# MCU.net
KiCad netlist of a schematic drawn in Altium Designer
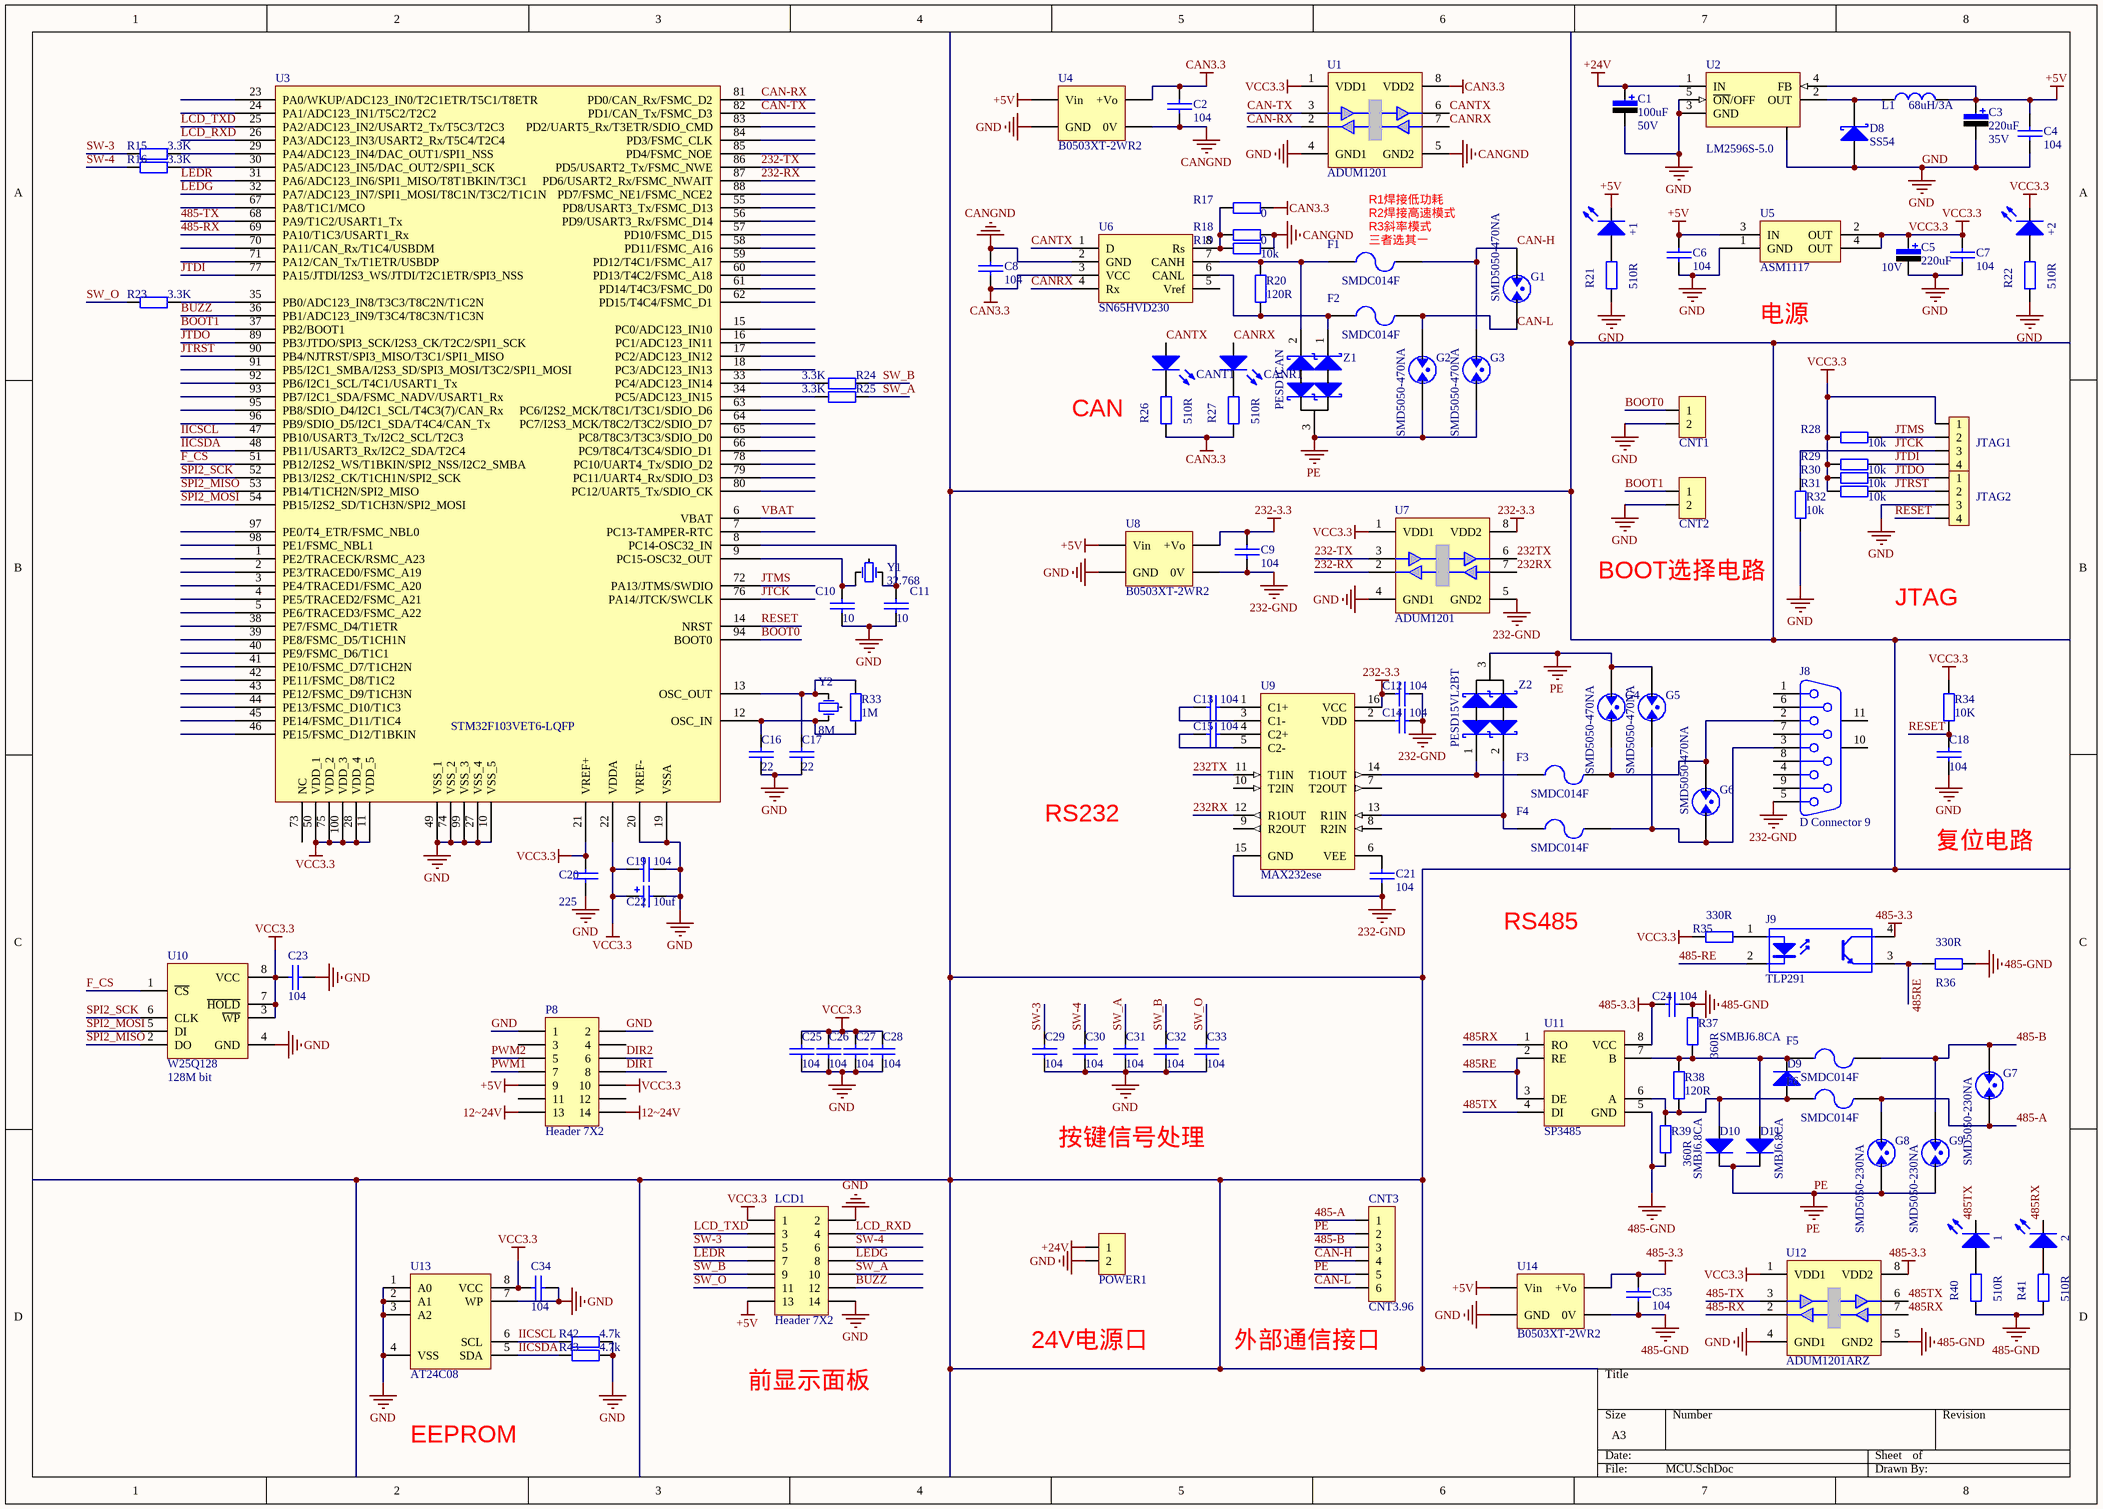
[diagram p0: MCU.SchDoc]

(export (version "E")
  (design (tool "Eeschema 10.0.6"))
  (components
    (comp (ref "+1") (value "COLOUR") (footprint "0603LED") (libsource (lib "MY_Library") (part "ledφ6")))
    (comp (ref "+2") (value "COLOUR") (footprint "0603LED") (libsource (lib "MY_Library") (part "ledφ6")))
    (comp (ref "1") (value "COLOUR") (footprint "0603LED") (libsource (lib "MY_Library") (part "ledφ6")))
    (comp (ref "2") (value "COLOUR") (footprint "0603LED") (libsource (lib "MY_Library") (part "ledφ6")))
    (comp (ref "C1")
      (value "100uF")
      (footprint "C-RB-S10")
      (description "极性电解电容")
      (fields
        (field (name "VOL") "50V")
        (field (name "Comment") "Cap Pol")
        (field (name "PUBLISHER") "Altium Limited")
      )
      (libsource (lib "Fszhang") (part "Cap Pol"))
    )
    (comp (ref "C2")
      (value "104")
      (footprint "0603C")
      (description "安规电容")
      (libsource (lib "MY_Library") (part "CAP X"))
    )
    (comp (ref "C3")
      (value "220uF")
      (footprint "C-RB-S10")
      (description "极性电解电容")
      (fields
        (field (name "VOL") "35V")
        (field (name "Comment") "Cap Pol")
        (field (name "PUBLISHER") "Altium Limited")
      )
      (libsource (lib "Fszhang") (part "Cap Pol"))
    )
    (comp (ref "C4")
      (value "104")
      (footprint "0603C")
      (description "安规电容")
      (libsource (lib "MY_Library") (part "CAP X"))
    )
    (comp (ref "C5")
      (value "220uF")
      (footprint "CAP-7343")
      (description "极性电解电容")
      (fields
        (field (name "VOL") "10V")
        (field (name "Comment") "Cap Pol")
        (field (name "PUBLISHER") "Altium Limited")
      )
      (libsource (lib "Fszhang") (part "Cap Pol"))
    )
    (comp (ref "C6")
      (value "104")
      (footprint "0603C")
      (description "安规电容")
      (libsource (lib "MY_Library") (part "CAP X"))
    )
    (comp (ref "C7")
      (value "104")
      (footprint "0603C")
      (description "安规电容")
      (libsource (lib "MY_Library") (part "CAP X"))
    )
    (comp (ref "C8")
      (value "104")
      (footprint "0603C")
      (description "安规电容")
      (libsource (lib "MY_Library") (part "CAP X"))
    )
    (comp (ref "C9")
      (value "104")
      (footprint "0603C")
      (description "安规电容")
      (libsource (lib "MY_Library") (part "CAP X"))
    )
    (comp (ref "C10")
      (value "10")
      (footprint "0603C")
      (description "安规电容")
      (libsource (lib "MY_Library") (part "CAP X"))
    )
    (comp (ref "C11")
      (value "10")
      (footprint "0603C")
      (description "安规电容")
      (libsource (lib "MY_Library") (part "CAP X"))
    )
    (comp (ref "C12")
      (value "104")
      (footprint "0603C")
      (description "安规电容")
      (libsource (lib "MY_Library") (part "CAP X"))
    )
    (comp (ref "C13")
      (value "104")
      (footprint "0603C")
      (description "安规电容")
      (libsource (lib "MY_Library") (part "CAP X"))
    )
    (comp (ref "C14")
      (value "104")
      (footprint "0603C")
      (description "安规电容")
      (libsource (lib "MY_Library") (part "CAP X"))
    )
    (comp (ref "C15")
      (value "104")
      (footprint "0603C")
      (description "安规电容")
      (libsource (lib "MY_Library") (part "CAP X"))
    )
    (comp (ref "C16")
      (value "22")
      (footprint "0603C")
      (description "安规电容")
      (libsource (lib "MY_Library") (part "CAP X"))
    )
    (comp (ref "C17")
      (value "22")
      (footprint "0603C")
      (description "安规电容")
      (libsource (lib "MY_Library") (part "CAP X"))
    )
    (comp (ref "C18")
      (value "104")
      (footprint "0603C")
      (description "安规电容")
      (libsource (lib "MY_Library") (part "CAP X"))
    )
    (comp (ref "C19")
      (value "104")
      (footprint "0603C")
      (description "安规电容")
      (libsource (lib "MY_Library") (part "CAP X"))
    )
    (comp (ref "C20")
      (value "225")
      (footprint "0603C")
      (description "安规电容")
      (libsource (lib "MY_Library") (part "CAP X"))
    )
    (comp (ref "C21")
      (value "104")
      (footprint "0603C")
      (description "安规电容")
      (libsource (lib "MY_Library") (part "CAP X"))
    )
    (comp (ref "C22")
      (value "10uf")
      (footprint "ct3216-18")
      (description "电解电容")
      (libsource (lib "MY_Library") (part "CAP"))
    )
    (comp (ref "C23")
      (value "104")
      (footprint "0603C")
      (description "安规电容")
      (libsource (lib "MY_Library") (part "CAP X"))
    )
    (comp (ref "C24")
      (value "104")
      (footprint "0603C")
      (description "安规电容")
      (libsource (lib "MY_Library") (part "CAP X"))
    )
    (comp (ref "C25")
      (value "104")
      (footprint "0603C")
      (description "安规电容")
      (libsource (lib "MY_Library") (part "CAP X"))
    )
    (comp (ref "C26")
      (value "104")
      (footprint "0603C")
      (description "安规电容")
      (libsource (lib "MY_Library") (part "CAP X"))
    )
    (comp (ref "C27")
      (value "104")
      (footprint "0603C")
      (description "安规电容")
      (libsource (lib "MY_Library") (part "CAP X"))
    )
    (comp (ref "C28")
      (value "104")
      (footprint "0603C")
      (description "安规电容")
      (libsource (lib "MY_Library") (part "CAP X"))
    )
    (comp (ref "C29")
      (value "104")
      (footprint "0603C")
      (description "安规电容")
      (libsource (lib "MY_Library") (part "CAP X"))
    )
    (comp (ref "C30")
      (value "104")
      (footprint "0603C")
      (description "安规电容")
      (libsource (lib "MY_Library") (part "CAP X"))
    )
    (comp (ref "C31")
      (value "104")
      (footprint "0603C")
      (description "安规电容")
      (libsource (lib "MY_Library") (part "CAP X"))
    )
    (comp (ref "C32")
      (value "104")
      (footprint "0603C")
      (description "安规电容")
      (libsource (lib "MY_Library") (part "CAP X"))
    )
    (comp (ref "C33")
      (value "104")
      (footprint "0603C")
      (description "安规电容")
      (libsource (lib "MY_Library") (part "CAP X"))
    )
    (comp (ref "C34")
      (value "104")
      (footprint "0603C")
      (description "安规电容")
      (libsource (lib "MY_Library") (part "CAP X"))
    )
    (comp (ref "C35")
      (value "104")
      (footprint "0603C")
      (description "安规电容")
      (libsource (lib "MY_Library") (part "CAP X"))
    )
    (comp (ref "CANR1") (value "COLOUR") (footprint "0603LED") (libsource (lib "MY_Library") (part "ledφ6")))
    (comp (ref "CANT1") (value "COLOUR") (footprint "0603LED") (libsource (lib "MY_Library") (part "ledφ6")))
    (comp (ref "CNT1") (value "cnt2p") (footprint "cont-1") (libsource (lib "MY_Library") (part "cnt2p")))
    (comp (ref "CNT2") (value "cnt2p") (footprint "cont-1") (libsource (lib "MY_Library") (part "cnt2p")))
    (comp (ref "CNT3")
      (value "CNT3.96")
      (footprint "CNT3.96")
      (description "接线端子(3.96MM)")
      (libsource (lib "MY_Library") (part "CNT3.96"))
    )
    (comp (ref "D8")
      (value "D-Schottky")
      (footprint "DIODE-SMA")
      (description "肖特基二极管")
      (fields (field (name "TYPE") "SS54") (field (name "PUBLISHER") "Altium Limited"))
      (libsource (lib "Fszhang") (part "D-Schottky"))
    )
    (comp (ref "D9")
      (value "TVS")
      (footprint "DIODE-SMB")
      (description "TVS保护")
      (fields (field (name "TYPE") "SMBJ6.8CA") (field (name "PUBLISHER") "Altium Limited"))
      (libsource (lib "Fszhang") (part "TVS"))
    )
    (comp (ref "D10")
      (value "TVS")
      (footprint "DIODE-SMB")
      (description "TVS保护")
      (fields (field (name "TYPE") "SMBJ6.8CA") (field (name "PUBLISHER") "Altium Limited"))
      (libsource (lib "Fszhang") (part "TVS"))
    )
    (comp (ref "D11")
      (value "TVS")
      (footprint "DIODE-SMB")
      (description "TVS保护")
      (fields (field (name "TYPE") "SMBJ6.8CA") (field (name "PUBLISHER") "Altium Limited"))
      (libsource (lib "Fszhang") (part "TVS"))
    )
    (comp (ref "F1")
      (value "SMDC014F")
      (footprint "1812")
      (description "保险丝")
      (fields (field (name "PUBLISHER") "Altium Limited"))
      (libsource (lib "Fszhang") (part "Fuse 2"))
    )
    (comp (ref "F2")
      (value "SMDC014F")
      (footprint "1812")
      (description "保险丝")
      (fields (field (name "Comment") "Fuse") (field (name "PUBLISHER") "Altium Limited"))
      (libsource (lib "Fszhang") (part "Fuse 2"))
    )
    (comp (ref "F3")
      (value "SMDC014F")
      (footprint "1812")
      (description "保险丝")
      (fields (field (name "PUBLISHER") "Altium Limited"))
      (libsource (lib "Fszhang") (part "Fuse 2"))
    )
    (comp (ref "F4")
      (value "SMDC014F")
      (footprint "1812")
      (description "保险丝")
      (fields (field (name "Comment") "Fuse") (field (name "PUBLISHER") "Altium Limited"))
      (libsource (lib "Fszhang") (part "Fuse 2"))
    )
    (comp (ref "F5")
      (value "SMDC014F")
      (footprint "1812")
      (description "保险丝")
      (fields (field (name "PUBLISHER") "Altium Limited"))
      (libsource (lib "Fszhang") (part "Fuse 2"))
    )
    (comp (ref "F6")
      (value "SMDC014F")
      (footprint "1812")
      (description "保险丝")
      (fields (field (name "Comment") "Fuse") (field (name "PUBLISHER") "Altium Limited"))
      (libsource (lib "Fszhang") (part "Fuse 2"))
    )
    (comp (ref "G1")
      (value "SMD5050-470NA")
      (footprint "SMD5050")
      (description "230V 气体放电管")
      (libsource (lib "Fszhang") (part "SMD5050-230NA"))
    )
    (comp (ref "G2")
      (value "SMD5050-470NA")
      (footprint "SMD5050")
      (description "230V 气体放电管")
      (libsource (lib "Fszhang") (part "SMD5050-230NA"))
    )
    (comp (ref "G3")
      (value "SMD5050-470NA")
      (footprint "SMD5050")
      (description "230V 气体放电管")
      (libsource (lib "Fszhang") (part "SMD5050-230NA"))
    )
    (comp (ref "G4")
      (value "SMD5050-470NA")
      (footprint "SMD5050")
      (description "230V 气体放电管")
      (libsource (lib "Fszhang") (part "SMD5050-230NA"))
    )
    (comp (ref "G5")
      (value "SMD5050-470NA")
      (footprint "SMD5050")
      (description "230V 气体放电管")
      (libsource (lib "Fszhang") (part "SMD5050-230NA"))
    )
    (comp (ref "G6")
      (value "SMD5050-470NA")
      (footprint "SMD5050")
      (description "230V 气体放电管")
      (libsource (lib "Fszhang") (part "SMD5050-230NA"))
    )
    (comp (ref "G7")
      (value "SMD5050-230NA")
      (footprint "SMD5050")
      (description "230V 气体放电管")
      (libsource (lib "Fszhang") (part "SMD5050-230NA"))
    )
    (comp (ref "G8")
      (value "SMD5050-230NA")
      (footprint "SMD5050")
      (description "230V 气体放电管")
      (libsource (lib "Fszhang") (part "SMD5050-230NA"))
    )
    (comp (ref "G9")
      (value "SMD5050-230NA")
      (footprint "SMD5050")
      (description "230V 气体放电管")
      (libsource (lib "Fszhang") (part "SMD5050-230NA"))
    )
    (comp (ref "J8")
      (value "D Connector 9")
      (footprint "DB9-M")
      (description "串口")
      (fields (field (name "PUBLISHER") "Altium Limited"))
      (libsource (lib "Fszhang") (part "D Connector 9"))
    )
    (comp (ref "J9")
      (value "TLP291")
      (footprint "SOP127P710X350-4N")
      (description "光耦")
      (fields (field (name "PUBLISHER") "Altium Limited"))
      (libsource (lib "Fszhang") (part "TLP281"))
    )
    (comp (ref "JTAG1")
      (value "单排插针11mm4p")
      (footprint "单排插针2.54")
      (libsource (lib "MY_Library") (part "单排插针11mm4p"))
    )
    (comp (ref "JTAG2")
      (value "单排插针11mm4p")
      (footprint "单排插针2.54")
      (libsource (lib "MY_Library") (part "单排插针11mm4p"))
    )
    (comp (ref "L1")
      (value "68uH/3A")
      (footprint "L-SMD-12")
      (description "电感")
      (fields (field (name "Comment") "Inductor") (field (name "PUBLISHER") "Altium Limited"))
      (libsource (lib "Fszhang") (part "Inductor"))
    )
    (comp (ref "LCD1")
      (value "Header 7X2")
      (footprint "HDR7X2_A1")
      (description "Header, 7-Pin")
      (fields (field (name "PUBLISHER") "Altium Limited"))
      (libsource (lib "Fszhang") (part "Header 7X2"))
    )
    (comp (ref "P8")
      (value "Header 7X2")
      (footprint "HDR7X2_A1")
      (description "Header, 7-Pin")
      (fields (field (name "PUBLISHER") "Altium Limited"))
      (libsource (lib "Fszhang") (part "Header 7X2"))
    )
    (comp (ref "POWER1")
      (value "CNT5.08MM*2 WAN")
      (footprint "CNT5.08*2WAN")
      (libsource (lib "MY_Library") (part "CNT5.08MM*2 WAN"))
    )
    (comp (ref "R15")
      (value "3.3K")
      (footprint "0603-1")
      (description "贴片电阻")
      (fields (field (name "Comment") "Res1") (field (name "PUBLISHER") "Altium Limited"))
      (libsource (lib "") (part "Res1_1"))
    )
    (comp (ref "R16")
      (value "3.3K")
      (footprint "0603-1")
      (description "贴片电阻")
      (fields (field (name "Comment") "Res1") (field (name "PUBLISHER") "Altium Limited"))
      (libsource (lib "") (part "Res1_1"))
    )
    (comp (ref "R17")
      (value "0")
      (footprint "0603-1")
      (description "贴片电阻")
      (fields (field (name "Comment") "Res1") (field (name "PUBLISHER") "Altium Limited"))
      (libsource (lib "") (part "Res1_1"))
    )
    (comp (ref "R18")
      (value "0")
      (footprint "0603-1")
      (description "贴片电阻")
      (fields (field (name "Comment") "Res1") (field (name "PUBLISHER") "Altium Limited"))
      (libsource (lib "") (part "Res1_1"))
    )
    (comp (ref "R19")
      (value "10k")
      (footprint "0603-1")
      (description "贴片电阻")
      (fields (field (name "Comment") "Res1") (field (name "PUBLISHER") "Altium Limited"))
      (libsource (lib "") (part "Res1_1"))
    )
    (comp (ref "R20")
      (value "120R")
      (footprint "0603-1")
      (description "贴片电阻")
      (fields (field (name "Comment") "Res1") (field (name "PUBLISHER") "Altium Limited"))
      (libsource (lib "Fszhang") (part "Res1"))
    )
    (comp (ref "R21")
      (value "510R")
      (footprint "0603-1")
      (description "贴片电阻")
      (fields (field (name "Comment") "Res1") (field (name "PUBLISHER") "Altium Limited"))
      (libsource (lib "Fszhang") (part "Res1"))
    )
    (comp (ref "R22")
      (value "510R")
      (footprint "0603-1")
      (description "贴片电阻")
      (fields (field (name "Comment") "Res1") (field (name "PUBLISHER") "Altium Limited"))
      (libsource (lib "Fszhang") (part "Res1"))
    )
    (comp (ref "R23")
      (value "3.3K")
      (footprint "0603-1")
      (description "贴片电阻")
      (fields (field (name "Comment") "Res1") (field (name "PUBLISHER") "Altium Limited"))
      (libsource (lib "") (part "Res1_1"))
    )
    (comp (ref "R24")
      (value "3.3K")
      (footprint "0603-1")
      (description "贴片电阻")
      (fields (field (name "Comment") "Res1") (field (name "PUBLISHER") "Altium Limited"))
      (libsource (lib "") (part "Res1_2"))
    )
    (comp (ref "R25")
      (value "3.3K")
      (footprint "0603-1")
      (description "贴片电阻")
      (fields (field (name "Comment") "Res1") (field (name "PUBLISHER") "Altium Limited"))
      (libsource (lib "") (part "Res1_2"))
    )
    (comp (ref "R26")
      (value "510R")
      (footprint "0603-1")
      (description "贴片电阻")
      (fields (field (name "Comment") "Res1") (field (name "PUBLISHER") "Altium Limited"))
      (libsource (lib "Fszhang") (part "Res1"))
    )
    (comp (ref "R27")
      (value "510R")
      (footprint "0603-1")
      (description "贴片电阻")
      (fields (field (name "Comment") "Res1") (field (name "PUBLISHER") "Altium Limited"))
      (libsource (lib "Fszhang") (part "Res1"))
    )
    (comp (ref "R28")
      (value "10k")
      (footprint "0603-1")
      (description "贴片电阻")
      (fields (field (name "Comment") "Res1") (field (name "PUBLISHER") "Altium Limited"))
      (libsource (lib "") (part "Res1_1"))
    )
    (comp (ref "R29")
      (value "10k")
      (footprint "0603-1")
      (description "贴片电阻")
      (fields (field (name "Comment") "Res1") (field (name "PUBLISHER") "Altium Limited"))
      (libsource (lib "") (part "Res1_1"))
    )
    (comp (ref "R30")
      (value "10k")
      (footprint "0603-1")
      (description "贴片电阻")
      (fields (field (name "Comment") "Res1") (field (name "PUBLISHER") "Altium Limited"))
      (libsource (lib "") (part "Res1_1"))
    )
    (comp (ref "R31")
      (value "10k")
      (footprint "0603-1")
      (description "贴片电阻")
      (fields (field (name "Comment") "Res1") (field (name "PUBLISHER") "Altium Limited"))
      (libsource (lib "") (part "Res1_1"))
    )
    (comp (ref "R32")
      (value "10k")
      (footprint "0603-1")
      (description "贴片电阻")
      (fields (field (name "Comment") "Res1") (field (name "PUBLISHER") "Altium Limited"))
      (libsource (lib "") (part "Res1_3"))
    )
    (comp (ref "R33")
      (value "1M")
      (footprint "0603-1")
      (description "贴片电阻")
      (fields (field (name "Comment") "Res1") (field (name "PUBLISHER") "Altium Limited"))
      (libsource (lib "Fszhang") (part "Res1"))
    )
    (comp (ref "R34")
      (value "10K")
      (footprint "0603-1")
      (description "贴片电阻")
      (fields (field (name "Comment") "Res1") (field (name "PUBLISHER") "Altium Limited"))
      (libsource (lib "Fszhang") (part "Res1"))
    )
    (comp (ref "R35")
      (value "330R")
      (footprint "0603-1")
      (description "贴片电阻")
      (fields (field (name "Comment") "Res1") (field (name "PUBLISHER") "Altium Limited"))
      (libsource (lib "") (part "Res1_1"))
    )
    (comp (ref "R36")
      (value "330R")
      (footprint "0603-1")
      (description "贴片电阻")
      (fields (field (name "Comment") "Res1") (field (name "PUBLISHER") "Altium Limited"))
      (libsource (lib "") (part "Res1_1"))
    )
    (comp (ref "R37")
      (value "360R")
      (footprint "0603-1")
      (description "贴片电阻")
      (fields (field (name "Comment") "Res1") (field (name "PUBLISHER") "Altium Limited"))
      (libsource (lib "Fszhang") (part "Res1"))
    )
    (comp (ref "R38")
      (value "120R")
      (footprint "0603-1")
      (description "贴片电阻")
      (fields (field (name "Comment") "Res1") (field (name "PUBLISHER") "Altium Limited"))
      (libsource (lib "Fszhang") (part "Res1"))
    )
    (comp (ref "R39")
      (value "360R")
      (footprint "0603-1")
      (description "贴片电阻")
      (fields (field (name "Comment") "Res1") (field (name "PUBLISHER") "Altium Limited"))
      (libsource (lib "Fszhang") (part "Res1"))
    )
    (comp (ref "R40")
      (value "510R")
      (footprint "0603-1")
      (description "贴片电阻")
      (fields (field (name "Comment") "Res1") (field (name "PUBLISHER") "Altium Limited"))
      (libsource (lib "Fszhang") (part "Res1"))
    )
    (comp (ref "R41")
      (value "510R")
      (footprint "0603-1")
      (description "贴片电阻")
      (fields (field (name "Comment") "Res1") (field (name "PUBLISHER") "Altium Limited"))
      (libsource (lib "Fszhang") (part "Res1"))
    )
    (comp (ref "R42")
      (value "4.7k")
      (footprint "0603-1")
      (description "贴片电阻")
      (fields (field (name "Comment") "Res1") (field (name "PUBLISHER") "Altium Limited"))
      (libsource (lib "") (part "Res1_1"))
    )
    (comp (ref "R43")
      (value "4.7k")
      (footprint "0603-1")
      (description "贴片电阻")
      (fields (field (name "Comment") "Res1") (field (name "PUBLISHER") "Altium Limited"))
      (libsource (lib "") (part "Res1_1"))
    )
    (comp (ref "U1")
      (value "ADUM1201")
      (footprint "NSO8_N")
      (description "ADI隔离芯片")
      (libsource (lib "Fszhang") (part "ADUM1201"))
    )
    (comp (ref "U2")
      (value "LM2596S-5.0")
      (footprint "TO-263-5")
      (description "5V稳压芯片")
      (fields (field (name "PUBLISHER") "Altium Limited"))
      (libsource (lib "Fszhang") (part "LM2596S-5.0"))
    )
    (comp (ref "U3")
      (value "STM32F103VET6-LQFP")
      (footprint "LQFP-100_M")
      (description "STM32单片机100引脚")
      (libsource (lib "Fszhang") (part "STM32F103V"))
    )
    (comp (ref "U4")
      (value "B0503XT-2WR2")
      (footprint "B_XT-2WR2")
      (description "5v-3.3v-2w隔离电源")
      (libsource (lib "Fszhang") (part "B0503D-2WR2"))
    )
    (comp (ref "U5")
      (value "ASM1117")
      (footprint "SOT-223")
      (description "3.3V稳压芯片")
      (libsource (lib "Fszhang") (part "ASM1117"))
    )
    (comp (ref "U6")
      (value "SN65HVD230")
      (footprint "NSO8_N")
      (description "CAN芯片")
      (libsource (lib "Fszhang") (part "SN65HVD230"))
    )
    (comp (ref "U7")
      (value "ADUM1201")
      (footprint "NSO8_N")
      (description "ADI隔离芯片")
      (libsource (lib "Fszhang") (part "ADUM1201"))
    )
    (comp (ref "U8")
      (value "B0503XT-2WR2")
      (footprint "B_XT-2WR2")
      (description "5v-3.3v-2w隔离电源")
      (libsource (lib "Fszhang") (part "B0503D-2WR2"))
    )
    (comp (ref "U9")
      (value "MAX232ese")
      (footprint "NSO16_M")
      (description "+5V Powered, Multi-Channel RS-232 Driver/Receiver")
      (fields (field (name "PUBLISHER") "Altium Limited"))
      (libsource (lib "Fszhang") (part "MAX232"))
    )
    (comp (ref "U10")
      (value "W25Q128")
      (footprint "SOIC8_W")
      (description "SPI FLASH")
      (fields (field (name "MEMORY") "128M bit"))
      (libsource (lib "Fszhang") (part "W25QXX"))
    )
    (comp (ref "U11")
      (value "SP3485")
      (footprint "NSO8_N")
      (description "485总线芯片")
      (libsource (lib "Fszhang") (part "SP3485"))
    )
    (comp (ref "U12")
      (value "ADUM1201ARZ")
      (footprint "NSO8_N")
      (description "ADI隔离芯片")
      (libsource (lib "Fszhang") (part "ADUM1201"))
    )
    (comp (ref "U13")
      (value "AT24C08")
      (footprint "SOIC8_N")
      (description "EEROM存储器")
      (libsource (lib "Fszhang") (part "AT24C02"))
    )
    (comp (ref "U14")
      (value "B0503XT-2WR2")
      (footprint "B_XT-2WR2")
      (description "5v-3.3v-2w隔离电源")
      (libsource (lib "Fszhang") (part "B0503D-2WR2"))
    )
    (comp (ref "Y1")
      (value "32.768")
      (footprint "MC-146")
      (description "圆柱晶振")
      (fields (field (name "Comment") "XTAL_SM") (field (name "PUBLISHER") "Altium Limited"))
      (libsource (lib "Fszhang") (part "XTAL_SM"))
    )
    (comp (ref "Y2")
      (value "8M")
      (footprint "xtal3225")
      (description "圆柱晶振")
      (fields (field (name "Comment") "XTAL_SM") (field (name "PUBLISHER") "Altium Limited"))
      (libsource (lib "Fszhang") (part "XTAL_SM"))
    )
    (comp (ref "Z1")
      (value "PESD1CAN")
      (footprint "SOT-23")
      (description "过压保护")
      (libsource (lib "Fszhang") (part "PESD1CAN"))
    )
    (comp (ref "Z2")
      (value "PESD15VL2BT")
      (footprint "SOT-23")
      (description "过压保护")
      (libsource (lib "Fszhang") (part "PESD1CAN"))
    )
  )
  (nets
    (net (code "1") (name "+5V") (class "Default")
      (node (ref "+1") (pin "2") (pinfunction "-_2") (pintype "passive"))
      (node (ref "C3") (pin "1") (pinfunction "1_1") (pintype "passive"))
      (node (ref "C4") (pin "1") (pinfunction "1_1") (pintype "passive"))
      (node (ref "C6") (pin "1") (pinfunction "1_1") (pintype "passive"))
      (node (ref "L1") (pin "2") (pinfunction "2_2") (pintype "passive"))
      (node (ref "LCD1") (pin "13") (pinfunction "13_13") (pintype "passive"))
      (node (ref "P8") (pin "9") (pinfunction "9_9") (pintype "passive"))
      (node (ref "U14") (pin "14") (pinfunction "Vin_14") (pintype "passive"))
      (node (ref "U2") (pin "4") (pinfunction "FB_4") (pintype "input"))
      (node (ref "U4") (pin "14") (pinfunction "Vin_14") (pintype "passive"))
      (node (ref "U5") (pin "3") (pinfunction "IN_3") (pintype "passive"))
      (node (ref "U8") (pin "14") (pinfunction "Vin_14") (pintype "passive"))
    )
    (net (code "2") (name "+24V") (class "Default")
      (node (ref "C1") (pin "1") (pinfunction "1_1") (pintype "passive"))
      (node (ref "POWER1") (pin "1") (pinfunction "1_1") (pintype "passive"))
      (node (ref "U2") (pin "1") (pinfunction "IN_1") (pintype "power_in"))
    )
    (net (code "3") (name "/232-RX") (class "Default")
      (node (ref "U3") (pin "87") (pinfunction "PD6/USART2_Rx/FSMC_NWAIT_87") (pintype "passive"))
      (node (ref "U7") (pin "2") (pinfunction "Voa_2") (pintype "passive"))
    )
    (net (code "4") (name "/232-TX") (class "Default")
      (node (ref "U3") (pin "86") (pinfunction "PD5/USART2_Tx/FSMC_NWE_86") (pintype "passive"))
      (node (ref "U7") (pin "3") (pinfunction "Vib_3") (pintype "passive"))
    )
    (net (code "5") (name "/232RX") (class "Default")
      (node (ref "U7") (pin "7") (pinfunction "Via_7") (pintype "passive"))
      (node (ref "U9") (pin "12") (pinfunction "R1OUT_12") (pintype "output"))
    )
    (net (code "6") (name "/232TX") (class "Default")
      (node (ref "U7") (pin "6") (pinfunction "Vob_6") (pintype "passive"))
      (node (ref "U9") (pin "11") (pinfunction "T1IN_11") (pintype "input"))
    )
    (net (code "7") (name "/485-A") (class "Default")
      (node (ref "CNT3") (pin "1") (pinfunction "1_1") (pintype "passive"))
      (node (ref "F6") (pin "2") (pinfunction "2_2") (pintype "passive"))
      (node (ref "G7") (pin "2") (pinfunction "2_2") (pintype "passive"))
      (node (ref "G8") (pin "1") (pinfunction "1_1") (pintype "passive"))
    )
    (net (code "8") (name "/485-B") (class "Default")
      (node (ref "CNT3") (pin "3") (pinfunction "3_3") (pintype "passive"))
      (node (ref "F5") (pin "2") (pinfunction "2_2") (pintype "passive"))
      (node (ref "G7") (pin "1") (pinfunction "1_1") (pintype "passive"))
      (node (ref "G9") (pin "1") (pinfunction "1_1") (pintype "passive"))
    )
    (net (code "9") (name "/485-RE") (class "Default")
      (node (ref "J9") (pin "2") (pinfunction "K_2") (pintype "passive"))
    )
    (net (code "10") (name "/485-RX") (class "Default")
      (node (ref "U12") (pin "2") (pinfunction "Voa_2") (pintype "passive"))
      (node (ref "U3") (pin "69") (pinfunction "PA10/T1C3/USART1_Rx_69") (pintype "passive"))
    )
    (net (code "11") (name "/485-TX") (class "Default")
      (node (ref "U12") (pin "3") (pinfunction "Vib_3") (pintype "passive"))
      (node (ref "U3") (pin "68") (pinfunction "PA9/T1C2/USART1_Tx_68") (pintype "passive"))
    )
    (net (code "12") (name "/485RE") (class "Default")
      (node (ref "J9") (pin "3") (pinfunction "E_3") (pintype "passive"))
      (node (ref "R36") (pin "2") (pinfunction "2_2") (pintype "passive"))
      (node (ref "U11") (pin "2") (pinfunction "RE_2") (pintype "passive"))
      (node (ref "U11") (pin "3") (pinfunction "DE_3") (pintype "passive"))
    )
    (net (code "13") (name "/485RX") (class "Default")
      (node (ref "2") (pin "2") (pinfunction "-_2") (pintype "passive"))
      (node (ref "U11") (pin "1") (pinfunction "RO_1") (pintype "passive"))
      (node (ref "U12") (pin "7") (pinfunction "Via_7") (pintype "passive"))
    )
    (net (code "14") (name "/485TX") (class "Default")
      (node (ref "1") (pin "2") (pinfunction "-_2") (pintype "passive"))
      (node (ref "U11") (pin "4") (pinfunction "DI_4") (pintype "passive"))
      (node (ref "U12") (pin "6") (pinfunction "Vob_6") (pintype "passive"))
    )
    (net (code "15") (name "/BOOT0") (class "Default")
      (node (ref "CNT1") (pin "1") (pinfunction "1_1") (pintype "passive"))
      (node (ref "U3") (pin "94") (pinfunction "BOOT0_94") (pintype "passive"))
    )
    (net (code "16") (name "/BOOT1") (class "Default")
      (node (ref "CNT2") (pin "1") (pinfunction "1_1") (pintype "passive"))
      (node (ref "U3") (pin "37") (pinfunction "PB2/BOOT1_37") (pintype "passive"))
    )
    (net (code "17") (name "/BUZZ") (class "Default")
      (node (ref "LCD1") (pin "12") (pinfunction "12_12") (pintype "passive"))
      (node (ref "U3") (pin "36") (pinfunction "PB1/ADC123_IN9/T3C4/T8C3N/T1C3N_36") (pintype "passive"))
    )
    (net (code "18") (name "/CAN-H") (class "Default")
      (node (ref "CNT3") (pin "4") (pinfunction "4_4") (pintype "passive"))
      (node (ref "F1") (pin "2") (pinfunction "2_2") (pintype "passive"))
      (node (ref "G1") (pin "1") (pinfunction "1_1") (pintype "passive"))
      (node (ref "G3") (pin "1") (pinfunction "1_1") (pintype "passive"))
    )
    (net (code "19") (name "/CAN-L") (class "Default")
      (node (ref "CNT3") (pin "6") (pinfunction "6_6") (pintype "passive"))
      (node (ref "F2") (pin "2") (pinfunction "2_2") (pintype "passive"))
      (node (ref "G1") (pin "2") (pinfunction "2_2") (pintype "passive"))
      (node (ref "G2") (pin "1") (pinfunction "1_1") (pintype "passive"))
    )
    (net (code "20") (name "/CAN-RX") (class "Default")
      (node (ref "U1") (pin "2") (pinfunction "Voa_2") (pintype "passive"))
      (node (ref "U3") (pin "81") (pinfunction "PD0/CAN_Rx/FSMC_D2_81") (pintype "passive"))
    )
    (net (code "21") (name "/CAN-TX") (class "Default")
      (node (ref "U1") (pin "3") (pinfunction "Vib_3") (pintype "passive"))
      (node (ref "U3") (pin "82") (pinfunction "PD1/CAN_Tx/FSMC_D3_82") (pintype "passive"))
    )
    (net (code "22") (name "/CANRX") (class "Default")
      (node (ref "CANR1") (pin "1") (pinfunction "+_1") (pintype "passive"))
      (node (ref "U1") (pin "7") (pinfunction "Via_7") (pintype "passive"))
      (node (ref "U6") (pin "4") (pinfunction "Rx_4") (pintype "passive"))
    )
    (net (code "23") (name "/CANTX") (class "Default")
      (node (ref "CANT1") (pin "1") (pinfunction "+_1") (pintype "passive"))
      (node (ref "U1") (pin "6") (pinfunction "Vob_6") (pintype "passive"))
      (node (ref "U6") (pin "1") (pinfunction "D_1") (pintype "passive"))
    )
    (net (code "24") (name "/DIR1") (class "Default")
      (node (ref "P8") (pin "8") (pinfunction "8_8") (pintype "passive"))
    )
    (net (code "25") (name "/DIR2") (class "Default")
      (node (ref "P8") (pin "6") (pinfunction "6_6") (pintype "passive"))
    )
    (net (code "26") (name "/F_CS") (class "Default")
      (node (ref "U10") (pin "1") (pinfunction "~{CS}_1") (pintype "passive"))
      (node (ref "U3") (pin "51") (pinfunction "PB12/I2S2_WS/T1BKIN/SPI2_NSS/I2C2_SMBA_51") (pintype "passive"))
    )
    (net (code "27") (name "/IICSCL") (class "Default")
      (node (ref "R42") (pin "2") (pinfunction "2_2") (pintype "passive"))
      (node (ref "U13") (pin "6") (pinfunction "SCL_6") (pintype "passive"))
      (node (ref "U3") (pin "47") (pinfunction "PB10/USART3_Tx/I2C2_SCL/T2C3_47") (pintype "passive"))
    )
    (net (code "28") (name "/IICSDA") (class "Default")
      (node (ref "R43") (pin "2") (pinfunction "2_2") (pintype "passive"))
      (node (ref "U13") (pin "5") (pinfunction "SDA_5") (pintype "passive"))
      (node (ref "U3") (pin "48") (pinfunction "PB11/USART3_Rx/I2C2_SDA/T2C4_48") (pintype "passive"))
    )
    (net (code "29") (name "/JTCK") (class "Default")
      (node (ref "JTAG1") (pin "3") (pinfunction "3_3") (pintype "passive"))
      (node (ref "R32") (pin "1") (pinfunction "1_1") (pintype "passive"))
      (node (ref "U3") (pin "76") (pinfunction "PA14/JTCK/SWCLK_76") (pintype "passive"))
    )
    (net (code "30") (name "/JTDI") (class "Default")
      (node (ref "JTAG1") (pin "4") (pinfunction "4_4") (pintype "passive"))
      (node (ref "R29") (pin "1") (pinfunction "1_1") (pintype "passive"))
      (node (ref "U3") (pin "77") (pinfunction "PA15/JTDI/I2S3_WS/JTDI/T2C1ETR/SPI3_NSS_77") (pintype "passive"))
    )
    (net (code "31") (name "/JTDO") (class "Default")
      (node (ref "JTAG2") (pin "1") (pinfunction "1_1") (pintype "passive"))
      (node (ref "R30") (pin "1") (pinfunction "1_1") (pintype "passive"))
      (node (ref "U3") (pin "89") (pinfunction "PB3/JTDO/SPI3_SCK/I2S3_CK/T2C2/SPI1_SCK_89") (pintype "passive"))
    )
    (net (code "32") (name "/JTMS") (class "Default")
      (node (ref "JTAG1") (pin "2") (pinfunction "2_2") (pintype "passive"))
      (node (ref "R28") (pin "1") (pinfunction "1_1") (pintype "passive"))
      (node (ref "U3") (pin "72") (pinfunction "PA13/JTMS/SWDIO_72") (pintype "passive"))
    )
    (net (code "33") (name "/JTRST") (class "Default")
      (node (ref "JTAG2") (pin "2") (pinfunction "2_2") (pintype "passive"))
      (node (ref "R31") (pin "1") (pinfunction "1_1") (pintype "passive"))
      (node (ref "U3") (pin "90") (pinfunction "PB4/NJTRST/SPI3_MISO/T3C1/SPI1_MISO_90") (pintype "passive"))
    )
    (net (code "34") (name "/LCD_RXD") (class "Default")
      (node (ref "LCD1") (pin "4") (pinfunction "4_4") (pintype "passive"))
      (node (ref "U3") (pin "26") (pinfunction "PA3/ADC123_IN3/USART2_Rx/T5C4/T2C4_26") (pintype "passive"))
    )
    (net (code "35") (name "/LCD_TXD") (class "Default")
      (node (ref "LCD1") (pin "3") (pinfunction "3_3") (pintype "passive"))
      (node (ref "U3") (pin "25") (pinfunction "PA2/ADC123_IN2/USART2_Tx/T5C3/T2C3_25") (pintype "passive"))
    )
    (net (code "36") (name "/LEDG") (class "Default")
      (node (ref "LCD1") (pin "8") (pinfunction "8_8") (pintype "passive"))
      (node (ref "U3") (pin "32") (pinfunction "PA7/ADC123_IN7/SPI1_MOSI/T8C1N/T3C2/T1C1N_32") (pintype "passive"))
    )
    (net (code "37") (name "/LEDR") (class "Default")
      (node (ref "LCD1") (pin "7") (pinfunction "7_7") (pintype "passive"))
      (node (ref "U3") (pin "31") (pinfunction "PA6/ADC123_IN6/SPI1_MISO/T8T1BKIN/T3C1_31") (pintype "passive"))
    )
    (net (code "38") (name "/PWM1") (class "Default")
      (node (ref "P8") (pin "7") (pinfunction "7_7") (pintype "passive"))
    )
    (net (code "39") (name "/PWM2") (class "Default")
      (node (ref "P8") (pin "5") (pinfunction "5_5") (pintype "passive"))
    )
    (net (code "40") (name "/RESET") (class "Default")
      (node (ref "C18") (pin "2") (pinfunction "2_2") (pintype "passive"))
      (node (ref "JTAG2") (pin "4") (pinfunction "4_4") (pintype "passive"))
      (node (ref "R34") (pin "1") (pinfunction "1_1") (pintype "passive"))
      (node (ref "U3") (pin "14") (pinfunction "NRST_14") (pintype "passive"))
    )
    (net (code "41") (name "/SPI2_MISO") (class "Default")
      (node (ref "U10") (pin "2") (pinfunction "DO_2") (pintype "passive"))
      (node (ref "U3") (pin "53") (pinfunction "PB14/T1CH2N/SPI2_MISO_53") (pintype "passive"))
    )
    (net (code "42") (name "/SPI2_MOSI") (class "Default")
      (node (ref "U10") (pin "5") (pinfunction "DI_5") (pintype "passive"))
      (node (ref "U3") (pin "54") (pinfunction "PB15/I2S2_SD/T1CH3N/SPI2_MOSI_54") (pintype "passive"))
    )
    (net (code "43") (name "/SPI2_SCK") (class "Default")
      (node (ref "U10") (pin "6") (pinfunction "CLK_6") (pintype "passive"))
      (node (ref "U3") (pin "52") (pinfunction "PB13/I2S2_CK/T1CH1N/SPI2_SCK_52") (pintype "passive"))
    )
    (net (code "44") (name "/SW-3") (class "Default")
      (node (ref "C29") (pin "1") (pinfunction "1_1") (pintype "passive"))
      (node (ref "LCD1") (pin "5") (pinfunction "5_5") (pintype "passive"))
      (node (ref "R15") (pin "2") (pinfunction "2_2") (pintype "passive"))
    )
    (net (code "45") (name "/SW-4") (class "Default")
      (node (ref "C30") (pin "1") (pinfunction "1_1") (pintype "passive"))
      (node (ref "LCD1") (pin "6") (pinfunction "6_6") (pintype "passive"))
      (node (ref "R16") (pin "2") (pinfunction "2_2") (pintype "passive"))
    )
    (net (code "46") (name "/SW_A") (class "Default")
      (node (ref "C31") (pin "1") (pinfunction "1_1") (pintype "passive"))
      (node (ref "LCD1") (pin "10") (pinfunction "10_10") (pintype "passive"))
      (node (ref "R25") (pin "2") (pinfunction "2_2") (pintype "passive"))
    )
    (net (code "47") (name "/SW_B") (class "Default")
      (node (ref "C32") (pin "1") (pinfunction "1_1") (pintype "passive"))
      (node (ref "LCD1") (pin "9") (pinfunction "9_9") (pintype "passive"))
      (node (ref "R24") (pin "2") (pinfunction "2_2") (pintype "passive"))
    )
    (net (code "48") (name "/SW_O") (class "Default")
      (node (ref "C33") (pin "1") (pinfunction "1_1") (pintype "passive"))
      (node (ref "LCD1") (pin "11") (pinfunction "11_11") (pintype "passive"))
      (node (ref "R23") (pin "2") (pinfunction "2_2") (pintype "passive"))
    )
    (net (code "49") (name "/VBAT") (class "Default")
      (node (ref "U3") (pin "6") (pinfunction "VBAT_6") (pintype "passive"))
    )
    (net (code "50") (name "12~24V") (class "Default")
      (node (ref "P8") (pin "13") (pinfunction "13_13") (pintype "passive"))
      (node (ref "P8") (pin "14") (pinfunction "14_14") (pintype "passive"))
    )
    (net (code "51") (name "232-3.3") (class "Default")
      (node (ref "C12") (pin "2") (pinfunction "2_2") (pintype "passive"))
      (node (ref "C9") (pin "1") (pinfunction "1_1") (pintype "passive"))
      (node (ref "U7") (pin "8") (pinfunction "VDD2_8") (pintype "passive"))
      (node (ref "U8") (pin "9") (pinfunction "+Vo_9") (pintype "passive"))
      (node (ref "U9") (pin "16") (pinfunction "VCC_16") (pintype "power_in"))
    )
    (net (code "52") (name "232-GND") (class "Default")
      (node (ref "C12") (pin "1") (pinfunction "1_1") (pintype "passive"))
      (node (ref "C14") (pin "1") (pinfunction "1_1") (pintype "passive"))
      (node (ref "C21") (pin "1") (pinfunction "1_1") (pintype "passive"))
      (node (ref "C9") (pin "2") (pinfunction "2_2") (pintype "passive"))
      (node (ref "J8") (pin "5") (pinfunction "5_5") (pintype "passive"))
      (node (ref "U7") (pin "5") (pinfunction "GND2_5") (pintype "passive"))
      (node (ref "U8") (pin "8") (pinfunction "0V_8") (pintype "passive"))
      (node (ref "U9") (pin "15") (pinfunction "GND_15") (pintype "power_in"))
    )
    (net (code "53") (name "485-3.3") (class "Default")
      (node (ref "C24") (pin "2") (pinfunction "2_2") (pintype "passive"))
      (node (ref "C35") (pin "1") (pinfunction "1_1") (pintype "passive"))
      (node (ref "J9") (pin "4") (pinfunction "C_4") (pintype "passive"))
      (node (ref "U11") (pin "8") (pinfunction "VCC_8") (pintype "passive"))
      (node (ref "U12") (pin "8") (pinfunction "VDD2_8") (pintype "passive"))
      (node (ref "U14") (pin "9") (pinfunction "+Vo_9") (pintype "passive"))
    )
    (net (code "54") (name "485-GND") (class "Default")
      (node (ref "C24") (pin "1") (pinfunction "1_1") (pintype "passive"))
      (node (ref "C35") (pin "2") (pinfunction "2_2") (pintype "passive"))
      (node (ref "R36") (pin "1") (pinfunction "1_1") (pintype "passive"))
      (node (ref "R37") (pin "2") (pinfunction "2_2") (pintype "passive"))
      (node (ref "R39") (pin "1") (pinfunction "1_1") (pintype "passive"))
      (node (ref "R40") (pin "1") (pinfunction "1_1") (pintype "passive"))
      (node (ref "R41") (pin "1") (pinfunction "1_1") (pintype "passive"))
      (node (ref "U11") (pin "5") (pinfunction "GND_5") (pintype "passive"))
      (node (ref "U12") (pin "5") (pinfunction "GND2_5") (pintype "passive"))
      (node (ref "U14") (pin "8") (pinfunction "0V_8") (pintype "passive"))
    )
    (net (code "55") (name "CAN3.3") (class "Default")
      (node (ref "C2") (pin "1") (pinfunction "1_1") (pintype "passive"))
      (node (ref "C8") (pin "2") (pinfunction "2_2") (pintype "passive"))
      (node (ref "R17") (pin "1") (pinfunction "1_1") (pintype "passive"))
      (node (ref "R26") (pin "1") (pinfunction "1_1") (pintype "passive"))
      (node (ref "R27") (pin "1") (pinfunction "1_1") (pintype "passive"))
      (node (ref "U1") (pin "8") (pinfunction "VDD2_8") (pintype "passive"))
      (node (ref "U4") (pin "9") (pinfunction "+Vo_9") (pintype "passive"))
      (node (ref "U6") (pin "3") (pinfunction "VCC_3") (pintype "passive"))
    )
    (net (code "56") (name "CANGND") (class "Default")
      (node (ref "C2") (pin "2") (pinfunction "2_2") (pintype "passive"))
      (node (ref "C8") (pin "1") (pinfunction "1_1") (pintype "passive"))
      (node (ref "R18") (pin "1") (pinfunction "1_1") (pintype "passive"))
      (node (ref "R19") (pin "1") (pinfunction "1_1") (pintype "passive"))
      (node (ref "U1") (pin "5") (pinfunction "GND2_5") (pintype "passive"))
      (node (ref "U4") (pin "8") (pinfunction "0V_8") (pintype "passive"))
      (node (ref "U6") (pin "2") (pinfunction "GND_2") (pintype "passive"))
    )
    (net (code "57") (name "GND") (class "Default")
      (node (ref "C1") (pin "2") (pinfunction "2_2") (pintype "passive"))
      (node (ref "C10") (pin "2") (pinfunction "2_2") (pintype "passive"))
      (node (ref "C11") (pin "2") (pinfunction "2_2") (pintype "passive"))
      (node (ref "C16") (pin "2") (pinfunction "2_2") (pintype "passive"))
      (node (ref "C17") (pin "2") (pinfunction "2_2") (pintype "passive"))
      (node (ref "C18") (pin "1") (pinfunction "1_1") (pintype "passive"))
      (node (ref "C19") (pin "1") (pinfunction "1_1") (pintype "passive"))
      (node (ref "C20") (pin "1") (pinfunction "1_1") (pintype "passive"))
      (node (ref "C22") (pin "2") (pinfunction "2_2") (pintype "passive"))
      (node (ref "C23") (pin "1") (pinfunction "1_1") (pintype "passive"))
      (node (ref "C25") (pin "1") (pinfunction "1_1") (pintype "passive"))
      (node (ref "C26") (pin "1") (pinfunction "1_1") (pintype "passive"))
      (node (ref "C27") (pin "1") (pinfunction "1_1") (pintype "passive"))
      (node (ref "C28") (pin "1") (pinfunction "1_1") (pintype "passive"))
      (node (ref "C29") (pin "2") (pinfunction "2_2") (pintype "passive"))
      (node (ref "C3") (pin "2") (pinfunction "2_2") (pintype "passive"))
      (node (ref "C30") (pin "2") (pinfunction "2_2") (pintype "passive"))
      (node (ref "C31") (pin "2") (pinfunction "2_2") (pintype "passive"))
      (node (ref "C32") (pin "2") (pinfunction "2_2") (pintype "passive"))
      (node (ref "C33") (pin "2") (pinfunction "2_2") (pintype "passive"))
      (node (ref "C34") (pin "1") (pinfunction "1_1") (pintype "passive"))
      (node (ref "C4") (pin "2") (pinfunction "2_2") (pintype "passive"))
      (node (ref "C5") (pin "2") (pinfunction "2_2") (pintype "passive"))
      (node (ref "C6") (pin "2") (pinfunction "2_2") (pintype "passive"))
      (node (ref "C7") (pin "2") (pinfunction "2_2") (pintype "passive"))
      (node (ref "CNT1") (pin "2") (pinfunction "2_2") (pintype "passive"))
      (node (ref "CNT2") (pin "2") (pinfunction "2_2") (pintype "passive"))
      (node (ref "D8") (pin "1") (pinfunction "A_1") (pintype "passive"))
      (node (ref "JTAG2") (pin "3") (pinfunction "3_3") (pintype "passive"))
      (node (ref "LCD1") (pin "14") (pinfunction "14_14") (pintype "passive"))
      (node (ref "LCD1") (pin "2") (pinfunction "2_2") (pintype "passive"))
      (node (ref "P8") (pin "1") (pinfunction "1_1") (pintype "passive"))
      (node (ref "P8") (pin "2") (pinfunction "2_2") (pintype "passive"))
      (node (ref "POWER1") (pin "2") (pinfunction "2_2") (pintype "passive"))
      (node (ref "R21") (pin "1") (pinfunction "1_1") (pintype "passive"))
      (node (ref "R22") (pin "1") (pinfunction "1_1") (pintype "passive"))
      (node (ref "R32") (pin "2") (pinfunction "2_2") (pintype "passive"))
      (node (ref "R42") (pin "1") (pinfunction "1_1") (pintype "passive"))
      (node (ref "R43") (pin "1") (pinfunction "1_1") (pintype "passive"))
      (node (ref "U1") (pin "4") (pinfunction "GND1_4") (pintype "passive"))
      (node (ref "U10") (pin "4") (pinfunction "GND_4") (pintype "passive"))
      (node (ref "U12") (pin "4") (pinfunction "GND1_4") (pintype "passive"))
      (node (ref "U13") (pin "1") (pinfunction "A0_1") (pintype "passive"))
      (node (ref "U13") (pin "2") (pinfunction "A1_2") (pintype "passive"))
      (node (ref "U13") (pin "3") (pinfunction "A2_3") (pintype "passive"))
      (node (ref "U13") (pin "4") (pinfunction "VSS_4") (pintype "passive"))
      (node (ref "U13") (pin "7") (pinfunction "WP_7") (pintype "passive"))
      (node (ref "U14") (pin "1") (pinfunction "GND_1") (pintype "passive"))
      (node (ref "U2") (pin "3") (pinfunction "GND_3") (pintype "power_in"))
      (node (ref "U2") (pin "5") (pinfunction "~{ON}/OFF_5") (pintype "input"))
      (node (ref "U2") (pin "6") (pinfunction "6_6") (pintype "power_in"))
      (node (ref "U3") (pin "10") (pinfunction "VSS_5_10") (pintype "passive"))
      (node (ref "U3") (pin "19") (pinfunction "VSSA_19") (pintype "passive"))
      (node (ref "U3") (pin "20") (pinfunction "VREF-_20") (pintype "passive"))
      (node (ref "U3") (pin "27") (pinfunction "VSS_4_27") (pintype "passive"))
      (node (ref "U3") (pin "49") (pinfunction "VSS_1_49") (pintype "passive"))
      (node (ref "U3") (pin "74") (pinfunction "VSS_2_74") (pintype "passive"))
      (node (ref "U3") (pin "99") (pinfunction "VSS_3_99") (pintype "passive"))
      (node (ref "U4") (pin "1") (pinfunction "GND_1") (pintype "passive"))
      (node (ref "U5") (pin "1") (pinfunction "GND_1") (pintype "passive"))
      (node (ref "U7") (pin "4") (pinfunction "GND1_4") (pintype "passive"))
      (node (ref "U8") (pin "1") (pinfunction "GND_1") (pintype "passive"))
    )
    (net (code "58") (name "Net-(+1-+)") (class "Default")
      (node (ref "+1") (pin "1") (pinfunction "+_1") (pintype "passive"))
      (node (ref "R21") (pin "2") (pinfunction "2_2") (pintype "passive"))
    )
    (net (code "59") (name "Net-(+2-+)") (class "Default")
      (node (ref "+2") (pin "1") (pinfunction "+_1") (pintype "passive"))
      (node (ref "R22") (pin "2") (pinfunction "2_2") (pintype "passive"))
    )
    (net (code "60") (name "Net-(1-+)") (class "Default")
      (node (ref "1") (pin "1") (pinfunction "+_1") (pintype "passive"))
      (node (ref "R40") (pin "2") (pinfunction "2_2") (pintype "passive"))
    )
    (net (code "61") (name "Net-(2-+)") (class "Default")
      (node (ref "2") (pin "1") (pinfunction "+_1") (pintype "passive"))
      (node (ref "R41") (pin "2") (pinfunction "2_2") (pintype "passive"))
    )
    (net (code "62") (name "Net-(CANR1--)") (class "Default")
      (node (ref "CANR1") (pin "2") (pinfunction "-_2") (pintype "passive"))
      (node (ref "R27") (pin "2") (pinfunction "2_2") (pintype "passive"))
    )
    (net (code "63") (name "Net-(CANT1--)") (class "Default")
      (node (ref "CANT1") (pin "2") (pinfunction "-_2") (pintype "passive"))
      (node (ref "R26") (pin "2") (pinfunction "2_2") (pintype "passive"))
    )
    (net (code "64") (name "Net-(D8-K)") (class "Default")
      (node (ref "D8") (pin "2") (pinfunction "K_2") (pintype "passive"))
      (node (ref "L1") (pin "1") (pinfunction "1_1") (pintype "passive"))
      (node (ref "U2") (pin "2") (pinfunction "OUT_2") (pintype "power_in"))
    )
    (net (code "65") (name "Net-(D10-A)") (class "Default")
      (node (ref "D10") (pin "1") (pinfunction "A_1") (pintype "passive"))
      (node (ref "D9") (pin "1") (pinfunction "A_1") (pintype "passive"))
      (node (ref "F6") (pin "1") (pinfunction "1_1") (pintype "passive"))
      (node (ref "R38") (pin "1") (pinfunction "1_1") (pintype "passive"))
      (node (ref "R39") (pin "2") (pinfunction "2_2") (pintype "passive"))
      (node (ref "U11") (pin "6") (pinfunction "A_6") (pintype "passive"))
    )
    (net (code "66") (name "Net-(D11-A)") (class "Default")
      (node (ref "D11") (pin "1") (pinfunction "A_1") (pintype "passive"))
      (node (ref "D9") (pin "2") (pinfunction "K_2") (pintype "passive"))
      (node (ref "F5") (pin "1") (pinfunction "1_1") (pintype "passive"))
      (node (ref "R37") (pin "1") (pinfunction "1_1") (pintype "passive"))
      (node (ref "R38") (pin "2") (pinfunction "2_2") (pintype "passive"))
      (node (ref "U11") (pin "7") (pinfunction "B_7") (pintype "passive"))
    )
    (net (code "67") (name "Net-(F3-Pad2)") (class "Default")
      (node (ref "F3") (pin "2") (pinfunction "2_2") (pintype "passive"))
      (node (ref "G4") (pin "2") (pinfunction "2_2") (pintype "passive"))
      (node (ref "G6") (pin "1") (pinfunction "1_1") (pintype "passive"))
      (node (ref "J8") (pin "2") (pinfunction "2_2") (pintype "passive"))
    )
    (net (code "68") (name "Net-(F4-Pad2)") (class "Default")
      (node (ref "F4") (pin "2") (pinfunction "2_2") (pintype "passive"))
      (node (ref "G5") (pin "2") (pinfunction "2_2") (pintype "passive"))
      (node (ref "G6") (pin "2") (pinfunction "2_2") (pintype "passive"))
      (node (ref "J8") (pin "3") (pinfunction "3_3") (pintype "passive"))
    )
    (net (code "69") (name "Net-(J9-A)") (class "Default")
      (node (ref "J9") (pin "1") (pinfunction "A_1") (pintype "passive"))
      (node (ref "R35") (pin "1") (pinfunction "1_1") (pintype "passive"))
    )
    (net (code "70") (name "Net-(U3-OSC_IN)") (class "Default")
      (node (ref "C16") (pin "1") (pinfunction "1_1") (pintype "passive"))
      (node (ref "R33") (pin "1") (pinfunction "1_1") (pintype "passive"))
      (node (ref "U3") (pin "12") (pinfunction "OSC_IN_12") (pintype "passive"))
      (node (ref "Y2") (pin "1") (pinfunction "OSC1_1") (pintype "passive"))
    )
    (net (code "71") (name "Net-(U3-OSC_OUT)") (class "Default")
      (node (ref "C17") (pin "1") (pinfunction "1_1") (pintype "passive"))
      (node (ref "R33") (pin "2") (pinfunction "2_2") (pintype "passive"))
      (node (ref "U3") (pin "13") (pinfunction "OSC_OUT_13") (pintype "passive"))
      (node (ref "Y2") (pin "2") (pinfunction "OSC2_2") (pintype "passive"))
    )
    (net (code "72") (name "Net-(U3-PA4{slash}ADC123_IN4{slash}DAC_OUT1{slash}SPI1_NSS)") (class "Default")
      (node (ref "R15") (pin "1") (pinfunction "1_1") (pintype "passive"))
      (node (ref "U3") (pin "29") (pinfunction "PA4/ADC123_IN4/DAC_OUT1/SPI1_NSS_29") (pintype "passive"))
    )
    (net (code "73") (name "Net-(U3-PA5{slash}ADC123_IN5{slash}DAC_OUT2{slash}SPI1_SCK)") (class "Default")
      (node (ref "R16") (pin "1") (pinfunction "1_1") (pintype "passive"))
      (node (ref "U3") (pin "30") (pinfunction "PA5/ADC123_IN5/DAC_OUT2/SPI1_SCK_30") (pintype "passive"))
    )
    (net (code "74") (name "Net-(U3-PB0{slash}ADC123_IN8{slash}T3C3{slash}T8C2N{slash}T1C2N)") (class "Default")
      (node (ref "R23") (pin "1") (pinfunction "1_1") (pintype "passive"))
      (node (ref "U3") (pin "35") (pinfunction "PB0/ADC123_IN8/T3C3/T8C2N/T1C2N_35") (pintype "passive"))
    )
    (net (code "75") (name "Net-(U3-PC4{slash}ADC123_IN14)") (class "Default")
      (node (ref "R24") (pin "1") (pinfunction "1_1") (pintype "passive"))
      (node (ref "U3") (pin "33") (pinfunction "PC4/ADC123_IN14_33") (pintype "passive"))
    )
    (net (code "76") (name "Net-(U3-PC5{slash}ADC123_IN15)") (class "Default")
      (node (ref "R25") (pin "1") (pinfunction "1_1") (pintype "passive"))
      (node (ref "U3") (pin "34") (pinfunction "PC5/ADC123_IN15_34") (pintype "passive"))
    )
    (net (code "77") (name "Net-(U3-PC14-OSC32_IN)") (class "Default")
      (node (ref "C11") (pin "1") (pinfunction "1_1") (pintype "passive"))
      (node (ref "U3") (pin "8") (pinfunction "PC14-OSC32_IN_8") (pintype "passive"))
      (node (ref "Y1") (pin "2") (pinfunction "OSC2_2") (pintype "passive"))
    )
    (net (code "78") (name "Net-(U3-PC15-OSC32_OUT)") (class "Default")
      (node (ref "C10") (pin "1") (pinfunction "1_1") (pintype "passive"))
      (node (ref "U3") (pin "9") (pinfunction "PC15-OSC32_OUT_9") (pintype "passive"))
      (node (ref "Y1") (pin "1") (pinfunction "OSC1_1") (pintype "passive"))
    )
    (net (code "79") (name "Net-(U6-CANH)") (class "Default")
      (node (ref "F1") (pin "1") (pinfunction "1_1") (pintype "passive"))
      (node (ref "R20") (pin "2") (pinfunction "2_2") (pintype "passive"))
      (node (ref "U6") (pin "7") (pinfunction "CANH_7") (pintype "passive"))
      (node (ref "Z1") (pin "2") (pintype "passive"))
    )
    (net (code "80") (name "Net-(U6-CANL)") (class "Default")
      (node (ref "F2") (pin "1") (pinfunction "1_1") (pintype "passive"))
      (node (ref "R20") (pin "1") (pinfunction "1_1") (pintype "passive"))
      (node (ref "U6") (pin "6") (pinfunction "CANL_6") (pintype "passive"))
      (node (ref "Z1") (pin "1") (pintype "passive"))
    )
    (net (code "81") (name "Net-(U6-Rs)") (class "Default")
      (node (ref "R17") (pin "2") (pinfunction "2_2") (pintype "passive"))
      (node (ref "R18") (pin "2") (pinfunction "2_2") (pintype "passive"))
      (node (ref "R19") (pin "2") (pinfunction "2_2") (pintype "passive"))
      (node (ref "U6") (pin "8") (pinfunction "Rs_8") (pintype "passive"))
    )
    (net (code "82") (name "Net-(U9-C1+)") (class "Default")
      (node (ref "C13") (pin "1") (pinfunction "1_1") (pintype "passive"))
      (node (ref "U9") (pin "1") (pinfunction "C1+_1") (pintype "passive"))
    )
    (net (code "83") (name "Net-(U9-C1-)") (class "Default")
      (node (ref "C13") (pin "2") (pinfunction "2_2") (pintype "passive"))
      (node (ref "U9") (pin "3") (pinfunction "C1-_3") (pintype "passive"))
    )
    (net (code "84") (name "Net-(U9-C2+)") (class "Default")
      (node (ref "C15") (pin "1") (pinfunction "1_1") (pintype "passive"))
      (node (ref "U9") (pin "4") (pinfunction "C2+_4") (pintype "passive"))
    )
    (net (code "85") (name "Net-(U9-C2-)") (class "Default")
      (node (ref "C15") (pin "2") (pinfunction "2_2") (pintype "passive"))
      (node (ref "U9") (pin "5") (pinfunction "C2-_5") (pintype "passive"))
    )
    (net (code "86") (name "Net-(U9-R1IN)") (class "Default")
      (node (ref "F4") (pin "1") (pinfunction "1_1") (pintype "passive"))
      (node (ref "U9") (pin "13") (pinfunction "R1IN_13") (pintype "input"))
      (node (ref "Z2") (pin "2") (pintype "passive"))
    )
    (net (code "87") (name "Net-(U9-T1OUT)") (class "Default")
      (node (ref "F3") (pin "1") (pinfunction "1_1") (pintype "passive"))
      (node (ref "U9") (pin "14") (pinfunction "T1OUT_14") (pintype "output"))
      (node (ref "Z2") (pin "1") (pintype "passive"))
    )
    (net (code "88") (name "Net-(U9-VDD)") (class "Default")
      (node (ref "C14") (pin "2") (pinfunction "2_2") (pintype "passive"))
      (node (ref "U9") (pin "2") (pinfunction "VDD_2") (pintype "power_in"))
    )
    (net (code "89") (name "Net-(U9-VEE)") (class "Default")
      (node (ref "C21") (pin "2") (pinfunction "2_2") (pintype "passive"))
      (node (ref "U9") (pin "6") (pinfunction "VEE_6") (pintype "power_in"))
    )
    (net (code "90") (name "PE") (class "Default")
      (node (ref "CNT3") (pin "2") (pinfunction "2_2") (pintype "passive"))
      (node (ref "CNT3") (pin "5") (pinfunction "5_5") (pintype "passive"))
      (node (ref "D10") (pin "2") (pinfunction "K_2") (pintype "passive"))
      (node (ref "D11") (pin "2") (pinfunction "K_2") (pintype "passive"))
      (node (ref "G2") (pin "2") (pinfunction "2_2") (pintype "passive"))
      (node (ref "G3") (pin "2") (pinfunction "2_2") (pintype "passive"))
      (node (ref "G4") (pin "1") (pinfunction "1_1") (pintype "passive"))
      (node (ref "G5") (pin "1") (pinfunction "1_1") (pintype "passive"))
      (node (ref "G8") (pin "2") (pinfunction "2_2") (pintype "passive"))
      (node (ref "G9") (pin "2") (pinfunction "2_2") (pintype "passive"))
      (node (ref "Z1") (pin "3") (pintype "passive"))
      (node (ref "Z2") (pin "3") (pintype "passive"))
    )
    (net (code "91") (name "VCC3.3") (class "Default")
      (node (ref "+2") (pin "2") (pinfunction "-_2") (pintype "passive"))
      (node (ref "C19") (pin "2") (pinfunction "2_2") (pintype "passive"))
      (node (ref "C20") (pin "2") (pinfunction "2_2") (pintype "passive"))
      (node (ref "C22") (pin "1") (pinfunction "1_1") (pintype "passive"))
      (node (ref "C23") (pin "2") (pinfunction "2_2") (pintype "passive"))
      (node (ref "C25") (pin "2") (pinfunction "2_2") (pintype "passive"))
      (node (ref "C26") (pin "2") (pinfunction "2_2") (pintype "passive"))
      (node (ref "C27") (pin "2") (pinfunction "2_2") (pintype "passive"))
      (node (ref "C28") (pin "2") (pinfunction "2_2") (pintype "passive"))
      (node (ref "C34") (pin "2") (pinfunction "2_2") (pintype "passive"))
      (node (ref "C5") (pin "1") (pinfunction "1_1") (pintype "passive"))
      (node (ref "C7") (pin "1") (pinfunction "1_1") (pintype "passive"))
      (node (ref "JTAG1") (pin "1") (pinfunction "1_1") (pintype "passive"))
      (node (ref "LCD1") (pin "1") (pinfunction "1_1") (pintype "passive"))
      (node (ref "P8") (pin "10") (pinfunction "10_10") (pintype "passive"))
      (node (ref "R28") (pin "2") (pinfunction "2_2") (pintype "passive"))
      (node (ref "R29") (pin "2") (pinfunction "2_2") (pintype "passive"))
      (node (ref "R30") (pin "2") (pinfunction "2_2") (pintype "passive"))
      (node (ref "R31") (pin "2") (pinfunction "2_2") (pintype "passive"))
      (node (ref "R34") (pin "2") (pinfunction "2_2") (pintype "passive"))
      (node (ref "R35") (pin "2") (pinfunction "2_2") (pintype "passive"))
      (node (ref "U1") (pin "1") (pinfunction "VDD1_1") (pintype "passive"))
      (node (ref "U10") (pin "3") (pinfunction "~{WP}_3") (pintype "passive"))
      (node (ref "U10") (pin "7") (pinfunction "~{HOLD}_7") (pintype "passive"))
      (node (ref "U10") (pin "8") (pinfunction "VCC_8") (pintype "passive"))
      (node (ref "U12") (pin "1") (pinfunction "VDD1_1") (pintype "passive"))
      (node (ref "U13") (pin "8") (pinfunction "VCC_8") (pintype "passive"))
      (node (ref "U3") (pin "100") (pinfunction "VDD_3_100") (pintype "passive"))
      (node (ref "U3") (pin "11") (pinfunction "VDD_5_11") (pintype "passive"))
      (node (ref "U3") (pin "21") (pinfunction "VREF+_21") (pintype "passive"))
      (node (ref "U3") (pin "22") (pinfunction "VDDA_22") (pintype "passive"))
      (node (ref "U3") (pin "28") (pinfunction "VDD_4_28") (pintype "passive"))
      (node (ref "U3") (pin "50") (pinfunction "VDD_1_50") (pintype "passive"))
      (node (ref "U3") (pin "75") (pinfunction "VDD_2_75") (pintype "passive"))
      (node (ref "U5") (pin "2") (pinfunction "OUT_2") (pintype "passive"))
      (node (ref "U5") (pin "4") (pinfunction "OUT_4") (pintype "passive"))
      (node (ref "U7") (pin "1") (pinfunction "VDD1_1") (pintype "passive"))
    )
    (net (code "92") (name "unconnected-(J8-MH1-Pad10)") (class "Default")
      (node (ref "J8") (pin "10") (pinfunction "MH1_10") (pintype "passive"))
    )
    (net (code "93") (name "unconnected-(J8-MH2-Pad11)") (class "Default")
      (node (ref "J8") (pin "11") (pinfunction "MH2_11") (pintype "passive"))
    )
    (net (code "94") (name "unconnected-(J8-Pad1)") (class "Default")
      (node (ref "J8") (pin "1") (pinfunction "1_1") (pintype "passive"))
    )
    (net (code "95") (name "unconnected-(J8-Pad4)") (class "Default")
      (node (ref "J8") (pin "4") (pinfunction "4_4") (pintype "passive"))
    )
    (net (code "96") (name "unconnected-(J8-Pad6)") (class "Default")
      (node (ref "J8") (pin "6") (pinfunction "6_6") (pintype "passive"))
    )
    (net (code "97") (name "unconnected-(J8-Pad7)") (class "Default")
      (node (ref "J8") (pin "7") (pinfunction "7_7") (pintype "passive"))
    )
    (net (code "98") (name "unconnected-(J8-Pad8)") (class "Default")
      (node (ref "J8") (pin "8") (pinfunction "8_8") (pintype "passive"))
    )
    (net (code "99") (name "unconnected-(J8-Pad9)") (class "Default")
      (node (ref "J8") (pin "9") (pinfunction "9_9") (pintype "passive"))
    )
    (net (code "100") (name "unconnected-(P8-Pad3)") (class "Default")
      (node (ref "P8") (pin "3") (pinfunction "3_3") (pintype "passive"))
    )
    (net (code "101") (name "unconnected-(P8-Pad4)") (class "Default")
      (node (ref "P8") (pin "4") (pinfunction "4_4") (pintype "passive"))
    )
    (net (code "102") (name "unconnected-(P8-Pad11)") (class "Default")
      (node (ref "P8") (pin "11") (pinfunction "11_11") (pintype "passive"))
    )
    (net (code "103") (name "unconnected-(P8-Pad12)") (class "Default")
      (node (ref "P8") (pin "12") (pinfunction "12_12") (pintype "passive"))
    )
    (net (code "104") (name "unconnected-(U3-NC-Pad73)") (class "Default")
      (node (ref "U3") (pin "73") (pinfunction "NC_73") (pintype "passive"))
    )
    (net (code "105") (name "unconnected-(U3-PA0{slash}WKUP{slash}ADC123_IN0{slash}T2C1ETR{slash}T5C1{slash}T8ETR-Pad23)") (class "Default")
      (node (ref "U3") (pin "23") (pinfunction "PA0/WKUP/ADC123_IN0/T2C1ETR/T5C1/T8ETR_23") (pintype "passive"))
    )
    (net (code "106") (name "unconnected-(U3-PA1{slash}ADC123_IN1{slash}T5C2{slash}T2C2-Pad24)") (class "Default")
      (node (ref "U3") (pin "24") (pinfunction "PA1/ADC123_IN1/T5C2/T2C2_24") (pintype "passive"))
    )
    (net (code "107") (name "unconnected-(U3-PA8{slash}T1C1{slash}MCO-Pad67)") (class "Default")
      (node (ref "U3") (pin "67") (pinfunction "PA8/T1C1/MCO_67") (pintype "passive"))
    )
    (net (code "108") (name "unconnected-(U3-PA11{slash}CAN_Rx{slash}T1C4{slash}USBDM-Pad70)") (class "Default")
      (node (ref "U3") (pin "70") (pinfunction "PA11/CAN_Rx/T1C4/USBDM_70") (pintype "passive"))
    )
    (net (code "109") (name "unconnected-(U3-PA12{slash}CAN_Tx{slash}T1ETR{slash}USBDP-Pad71)") (class "Default")
      (node (ref "U3") (pin "71") (pinfunction "PA12/CAN_Tx/T1ETR/USBDP_71") (pintype "passive"))
    )
    (net (code "110") (name "unconnected-(U3-PB5{slash}I2C1_SMBA{slash}I2S3_SD{slash}SPI3_MOSI{slash}T3C2{slash}SPI1_MOSI-Pad91)") (class "Default")
      (node (ref "U3") (pin "91") (pinfunction "PB5/I2C1_SMBA/I2S3_SD/SPI3_MOSI/T3C2/SPI1_MOSI_91") (pintype "passive"))
    )
    (net (code "111") (name "unconnected-(U3-PB6{slash}I2C1_SCL{slash}T4C1{slash}USART1_Tx-Pad92)") (class "Default")
      (node (ref "U3") (pin "92") (pinfunction "PB6/I2C1_SCL/T4C1/USART1_Tx_92") (pintype "passive"))
    )
    (net (code "112") (name "unconnected-(U3-PB7{slash}I2C1_SDA{slash}FSMC_NADV{slash}USART1_Rx-Pad93)") (class "Default")
      (node (ref "U3") (pin "93") (pinfunction "PB7/I2C1_SDA/FSMC_NADV/USART1_Rx_93") (pintype "passive"))
    )
    (net (code "113") (name "unconnected-(U3-PB8{slash}SDIO_D4{slash}I2C1_SCL{slash}T4C3(7){slash}CAN_Rx-Pad95)") (class "Default")
      (node (ref "U3") (pin "95") (pinfunction "PB8/SDIO_D4/I2C1_SCL/T4C3(7)/CAN_Rx_95") (pintype "passive"))
    )
    (net (code "114") (name "unconnected-(U3-PB9{slash}SDIO_D5{slash}I2C1_SDA{slash}T4C4{slash}CAN_Tx-Pad96)") (class "Default")
      (node (ref "U3") (pin "96") (pinfunction "PB9/SDIO_D5/I2C1_SDA/T4C4/CAN_Tx_96") (pintype "passive"))
    )
    (net (code "115") (name "unconnected-(U3-PC0{slash}ADC123_IN10-Pad15)") (class "Default")
      (node (ref "U3") (pin "15") (pinfunction "PC0/ADC123_IN10_15") (pintype "passive"))
    )
    (net (code "116") (name "unconnected-(U3-PC1{slash}ADC123_IN11-Pad16)") (class "Default")
      (node (ref "U3") (pin "16") (pinfunction "PC1/ADC123_IN11_16") (pintype "passive"))
    )
    (net (code "117") (name "unconnected-(U3-PC2{slash}ADC123_IN12-Pad17)") (class "Default")
      (node (ref "U3") (pin "17") (pinfunction "PC2/ADC123_IN12_17") (pintype "passive"))
    )
    (net (code "118") (name "unconnected-(U3-PC3{slash}ADC123_IN13-Pad18)") (class "Default")
      (node (ref "U3") (pin "18") (pinfunction "PC3/ADC123_IN13_18") (pintype "passive"))
    )
    (net (code "119") (name "unconnected-(U3-PC6{slash}I2S2_MCK{slash}T8C1{slash}T3C1{slash}SDIO_D6-Pad63)") (class "Default")
      (node (ref "U3") (pin "63") (pinfunction "PC6/I2S2_MCK/T8C1/T3C1/SDIO_D6_63") (pintype "passive"))
    )
    (net (code "120") (name "unconnected-(U3-PC7{slash}I2S3_MCK{slash}T8C2{slash}T3C2{slash}SDIO_D7-Pad64)") (class "Default")
      (node (ref "U3") (pin "64") (pinfunction "PC7/I2S3_MCK/T8C2/T3C2/SDIO_D7_64") (pintype "passive"))
    )
    (net (code "121") (name "unconnected-(U3-PC8{slash}T8C3{slash}T3C3{slash}SDIO_D0-Pad65)") (class "Default")
      (node (ref "U3") (pin "65") (pinfunction "PC8/T8C3/T3C3/SDIO_D0_65") (pintype "passive"))
    )
    (net (code "122") (name "unconnected-(U3-PC9{slash}T8C4{slash}T3C4{slash}SDIO_D1-Pad66)") (class "Default")
      (node (ref "U3") (pin "66") (pinfunction "PC9/T8C4/T3C4/SDIO_D1_66") (pintype "passive"))
    )
    (net (code "123") (name "unconnected-(U3-PC10{slash}UART4_Tx{slash}SDIO_D2-Pad78)") (class "Default")
      (node (ref "U3") (pin "78") (pinfunction "PC10/UART4_Tx/SDIO_D2_78") (pintype "passive"))
    )
    (net (code "124") (name "unconnected-(U3-PC11{slash}UART4_Rx{slash}SDIO_D3-Pad79)") (class "Default")
      (node (ref "U3") (pin "79") (pinfunction "PC11/UART4_Rx/SDIO_D3_79") (pintype "passive"))
    )
    (net (code "125") (name "unconnected-(U3-PC12{slash}UART5_Tx{slash}SDIO_CK-Pad80)") (class "Default")
      (node (ref "U3") (pin "80") (pinfunction "PC12/UART5_Tx/SDIO_CK_80") (pintype "passive"))
    )
    (net (code "126") (name "unconnected-(U3-PC13-TAMPER-RTC-Pad7)") (class "Default")
      (node (ref "U3") (pin "7") (pinfunction "PC13-TAMPER-RTC_7") (pintype "passive"))
    )
    (net (code "127") (name "unconnected-(U3-PD2{slash}UART5_Rx{slash}T3ETR{slash}SDIO_CMD-Pad83)") (class "Default")
      (node (ref "U3") (pin "83") (pinfunction "PD2/UART5_Rx/T3ETR/SDIO_CMD_83") (pintype "passive"))
    )
    (net (code "128") (name "unconnected-(U3-PD3{slash}FSMC_CLK-Pad84)") (class "Default")
      (node (ref "U3") (pin "84") (pinfunction "PD3/FSMC_CLK_84") (pintype "passive"))
    )
    (net (code "129") (name "unconnected-(U3-PD4{slash}FSMC_NOE-Pad85)") (class "Default")
      (node (ref "U3") (pin "85") (pinfunction "PD4/FSMC_NOE_85") (pintype "passive"))
    )
    (net (code "130") (name "unconnected-(U3-PD7{slash}FSMC_NE1{slash}FSMC_NCE2-Pad88)") (class "Default")
      (node (ref "U3") (pin "88") (pinfunction "PD7/FSMC_NE1/FSMC_NCE2_88") (pintype "passive"))
    )
    (net (code "131") (name "unconnected-(U3-PD8{slash}USART3_Tx{slash}FSMC_D13-Pad55)") (class "Default")
      (node (ref "U3") (pin "55") (pinfunction "PD8/USART3_Tx/FSMC_D13_55") (pintype "passive"))
    )
    (net (code "132") (name "unconnected-(U3-PD9{slash}USART3_Rx{slash}FSMC_D14-Pad56)") (class "Default")
      (node (ref "U3") (pin "56") (pinfunction "PD9/USART3_Rx/FSMC_D14_56") (pintype "passive"))
    )
    (net (code "133") (name "unconnected-(U3-PD10{slash}FSMC_D15-Pad57)") (class "Default")
      (node (ref "U3") (pin "57") (pinfunction "PD10/FSMC_D15_57") (pintype "passive"))
    )
    (net (code "134") (name "unconnected-(U3-PD11{slash}FSMC_A16-Pad58)") (class "Default")
      (node (ref "U3") (pin "58") (pinfunction "PD11/FSMC_A16_58") (pintype "passive"))
    )
    (net (code "135") (name "unconnected-(U3-PD12{slash}T4C1{slash}FSMC_A17-Pad59)") (class "Default")
      (node (ref "U3") (pin "59") (pinfunction "PD12/T4C1/FSMC_A17_59") (pintype "passive"))
    )
    (net (code "136") (name "unconnected-(U3-PD13{slash}T4C2{slash}FSMC_A18-Pad60)") (class "Default")
      (node (ref "U3") (pin "60") (pinfunction "PD13/T4C2/FSMC_A18_60") (pintype "passive"))
    )
    (net (code "137") (name "unconnected-(U3-PD14{slash}T4C3{slash}FSMC_D0-Pad61)") (class "Default")
      (node (ref "U3") (pin "61") (pinfunction "PD14/T4C3/FSMC_D0_61") (pintype "passive"))
    )
    (net (code "138") (name "unconnected-(U3-PD15{slash}T4C4{slash}FSMC_D1-Pad62)") (class "Default")
      (node (ref "U3") (pin "62") (pinfunction "PD15/T4C4/FSMC_D1_62") (pintype "passive"))
    )
    (net (code "139") (name "unconnected-(U3-PE0{slash}T4_ETR{slash}FSMC_NBL0-Pad97)") (class "Default")
      (node (ref "U3") (pin "97") (pinfunction "PE0/T4_ETR/FSMC_NBL0_97") (pintype "passive"))
    )
    (net (code "140") (name "unconnected-(U3-PE1{slash}FSMC_NBL1-Pad98)") (class "Default")
      (node (ref "U3") (pin "98") (pinfunction "PE1/FSMC_NBL1_98") (pintype "passive"))
    )
    (net (code "141") (name "unconnected-(U3-PE2{slash}TRACECK{slash}RSMC_A23-Pad1)") (class "Default")
      (node (ref "U3") (pin "1") (pinfunction "PE2/TRACECK/RSMC_A23_1") (pintype "passive"))
    )
    (net (code "142") (name "unconnected-(U3-PE3{slash}TRACED0{slash}FSMC_A19-Pad2)") (class "Default")
      (node (ref "U3") (pin "2") (pinfunction "PE3/TRACED0/FSMC_A19_2") (pintype "passive"))
    )
    (net (code "143") (name "unconnected-(U3-PE4{slash}TRACED1{slash}FSMC_A20-Pad3)") (class "Default")
      (node (ref "U3") (pin "3") (pinfunction "PE4/TRACED1/FSMC_A20_3") (pintype "passive"))
    )
    (net (code "144") (name "unconnected-(U3-PE5{slash}TRACED2{slash}FSMC_A21-Pad4)") (class "Default")
      (node (ref "U3") (pin "4") (pinfunction "PE5/TRACED2/FSMC_A21_4") (pintype "passive"))
    )
    (net (code "145") (name "unconnected-(U3-PE6{slash}TRACED3{slash}FSMC_A22-Pad5)") (class "Default")
      (node (ref "U3") (pin "5") (pinfunction "PE6/TRACED3/FSMC_A22_5") (pintype "passive"))
    )
    (net (code "146") (name "unconnected-(U3-PE7{slash}FSMC_D4{slash}T1ETR-Pad38)") (class "Default")
      (node (ref "U3") (pin "38") (pinfunction "PE7/FSMC_D4/T1ETR_38") (pintype "passive"))
    )
    (net (code "147") (name "unconnected-(U3-PE8{slash}FSMC_D5{slash}T1CH1N-Pad39)") (class "Default")
      (node (ref "U3") (pin "39") (pinfunction "PE8/FSMC_D5/T1CH1N_39") (pintype "passive"))
    )
    (net (code "148") (name "unconnected-(U3-PE9{slash}FSMC_D6{slash}T1C1-Pad40)") (class "Default")
      (node (ref "U3") (pin "40") (pinfunction "PE9/FSMC_D6/T1C1_40") (pintype "passive"))
    )
    (net (code "149") (name "unconnected-(U3-PE10{slash}FSMC_D7{slash}T1CH2N-Pad41)") (class "Default")
      (node (ref "U3") (pin "41") (pinfunction "PE10/FSMC_D7/T1CH2N_41") (pintype "passive"))
    )
    (net (code "150") (name "unconnected-(U3-PE11{slash}FSMC_D8{slash}T1C2-Pad42)") (class "Default")
      (node (ref "U3") (pin "42") (pinfunction "PE11/FSMC_D8/T1C2_42") (pintype "passive"))
    )
    (net (code "151") (name "unconnected-(U3-PE12{slash}FSMC_D9{slash}T1CH3N-Pad43)") (class "Default")
      (node (ref "U3") (pin "43") (pinfunction "PE12/FSMC_D9/T1CH3N_43") (pintype "passive"))
    )
    (net (code "152") (name "unconnected-(U3-PE13{slash}FSMC_D10{slash}T1C3-Pad44)") (class "Default")
      (node (ref "U3") (pin "44") (pinfunction "PE13/FSMC_D10/T1C3_44") (pintype "passive"))
    )
    (net (code "153") (name "unconnected-(U3-PE14{slash}FSMC_D11{slash}T1C4-Pad45)") (class "Default")
      (node (ref "U3") (pin "45") (pinfunction "PE14/FSMC_D11/T1C4_45") (pintype "passive"))
    )
    (net (code "154") (name "unconnected-(U3-PE15{slash}FSMC_D12{slash}T1BKIN-Pad46)") (class "Default")
      (node (ref "U3") (pin "46") (pinfunction "PE15/FSMC_D12/T1BKIN_46") (pintype "passive"))
    )
    (net (code "155") (name "unconnected-(U6-Vref-Pad5)") (class "Default")
      (node (ref "U6") (pin "5") (pinfunction "Vref_5") (pintype "passive"))
    )
    (net (code "156") (name "unconnected-(U9-R2IN-Pad8)") (class "Default")
      (node (ref "U9") (pin "8") (pinfunction "R2IN_8") (pintype "input"))
    )
    (net (code "157") (name "unconnected-(U9-R2OUT-Pad9)") (class "Default")
      (node (ref "U9") (pin "9") (pinfunction "R2OUT_9") (pintype "output"))
    )
    (net (code "158") (name "unconnected-(U9-T2IN-Pad10)") (class "Default")
      (node (ref "U9") (pin "10") (pinfunction "T2IN_10") (pintype "input"))
    )
    (net (code "159") (name "unconnected-(U9-T2OUT-Pad7)") (class "Default")
      (node (ref "U9") (pin "7") (pinfunction "T2OUT_7") (pintype "output"))
    )
    (net (code "160") (name "unconnected-(Y1-Pad3)") (class "Default")
      (node (ref "Y1") (pin "3") (pinfunction "3_3") (pintype "passive"))
    )
    (net (code "161") (name "unconnected-(Y2-Pad3)") (class "Default")
      (node (ref "Y2") (pin "3") (pinfunction "3_3") (pintype "passive"))
    )
  )
)
